# 03_-_Controller.net
KiCad netlist of a schematic drawn in Altium Designer
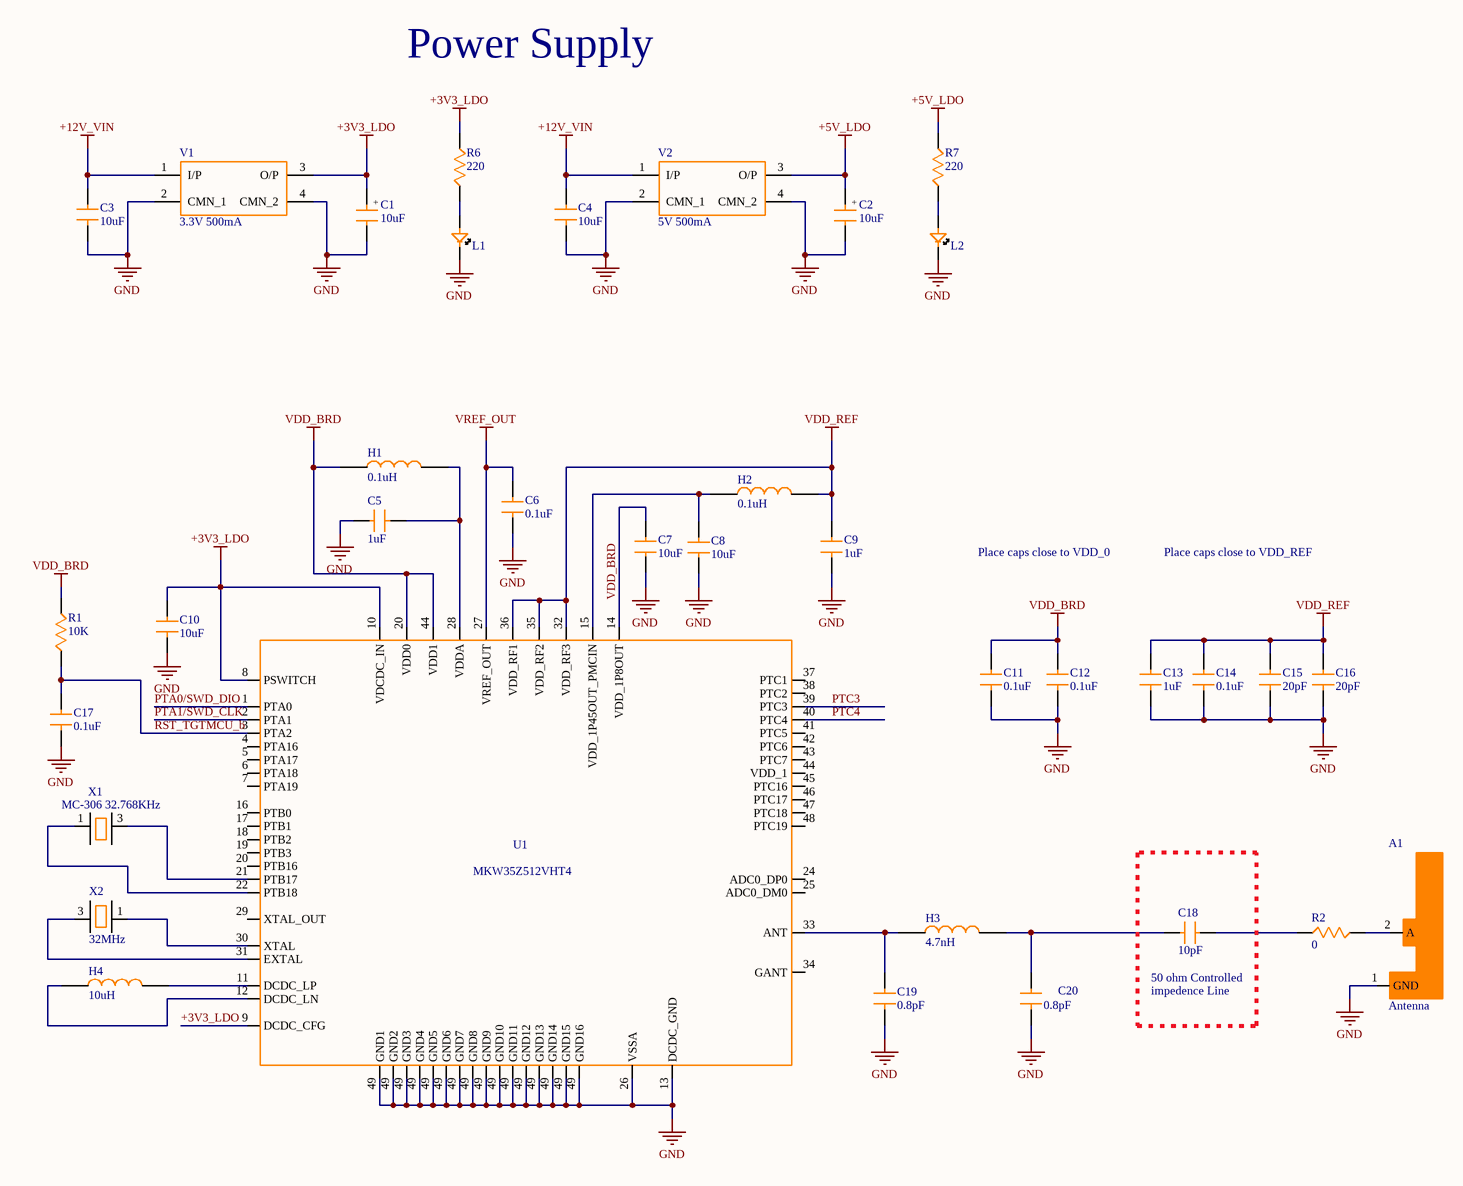
[diagram p0: [03] - Controller.SchDoc]

(export (version "E")
  (design (tool "Eeschema 10.0.6"))
  (components
    (comp (ref "A1")
      (value "Antenna")
      (footprint "Antenna")
      (libsource (lib "Joule_Library") (part "Antenna"))
    )
    (comp (ref "C1")
      (value "10uF")
      (footprint "C1206")
      (description "Tantalum Capacitors - Polymer SMD 10V 4.7uF 20% 1206 ESR=300mOhm")
      (fields
        (field (name "MANUFACTURER") "AVX")
        (field (name "MANUFACTURER PART NUMBER") "TCJK475M010R0300")
      )
      (libsource (lib "Joule_Library") (part "EIA_A-4.7uF,10V"))
    )
    (comp (ref "C2")
      (value "10uF")
      (footprint "C1206")
      (description "Tantalum Capacitors - Polymer SMD 10V 4.7uF 20% 1206 ESR=300mOhm")
      (fields
        (field (name "MANUFACTURER") "AVX")
        (field (name "MANUFACTURER PART NUMBER") "TCJK475M010R0300")
      )
      (libsource (lib "Joule_Library") (part "EIA_A-4.7uF,10V"))
    )
    (comp (ref "C3")
      (value "10uF")
      (footprint "C1206")
      (description "Multilayer Ceramic Capacitors MLCC - SMD/SMT 10uF Y5V -20/+80% 50V")
      (fields
        (field (name "MANUFACTURER") "Yageo")
        (field (name "MANUFACTURER PART NUMBER") "CC1210ZKY5V9BB106")
      )
      (libsource (lib "Joule_Library") (part "C_1206-10uF"))
    )
    (comp (ref "C4")
      (value "10uF")
      (footprint "C1206")
      (description "Multilayer Ceramic Capacitors MLCC - SMD/SMT 10uF Y5V -20/+80% 50V")
      (fields
        (field (name "MANUFACTURER") "Yageo")
        (field (name "MANUFACTURER PART NUMBER") "CC1210ZKY5V9BB106")
      )
      (libsource (lib "Joule_Library") (part "C_1206-10uF"))
    )
    (comp (ref "C5")
      (value "1uF")
      (footprint "C0805")
      (description "Multilayer Ceramic Capacitors MLCC - SMD/SMT 10V 1uF X7R 0805 10%")
      (fields
        (field (name "MANUFACTURER") "KEMET")
        (field (name "MANUFACTURER PART NUMBER") "C0805C105K8RAC7210")
      )
      (libsource (lib "Joule_Library") (part "C_0805-1uF"))
    )
    (comp (ref "C6")
      (value "0.1uF")
      (footprint "C0805")
      (description "Multilayer Ceramic Capacitors MLCC - SMD/SMT 0.1uF 10% 50V AEC-Q200")
      (fields
        (field (name "MANUFACTURER") "Yageo")
        (field (name "MANUFACTURER PART NUMBER") "AS0805KKX7R9BB104")
      )
      (libsource (lib "Joule_Library") (part "C_0805-0.1uF"))
    )
    (comp (ref "C7")
      (value "10uF")
      (footprint "C0805")
      (description "Multilayer Ceramic Capacitors MLCC - SMD/SMT 10uF 10% 25V")
      (fields
        (field (name "MANUFACTURER") "Yageo")
        (field (name "MANUFACTURER PART NUMBER") "CC0805KFX5R8BB106")
      )
      (libsource (lib "Joule_Library") (part "C_0805-10uF"))
    )
    (comp (ref "C8")
      (value "10uF")
      (footprint "C0805")
      (description "Multilayer Ceramic Capacitors MLCC - SMD/SMT 10uF 10% 25V")
      (fields
        (field (name "MANUFACTURER") "Yageo")
        (field (name "MANUFACTURER PART NUMBER") "CC0805KFX5R8BB106")
      )
      (libsource (lib "Joule_Library") (part "C_0805-10uF"))
    )
    (comp (ref "C9")
      (value "1uF")
      (footprint "C0805")
      (description "Multilayer Ceramic Capacitors MLCC - SMD/SMT 10V 1uF X7R 0805 10%")
      (fields
        (field (name "MANUFACTURER") "KEMET")
        (field (name "MANUFACTURER PART NUMBER") "C0805C105K8RAC7210")
      )
      (libsource (lib "Joule_Library") (part "C_0805-1uF"))
    )
    (comp (ref "C10")
      (value "10uF")
      (footprint "C1206")
      (description "Multilayer Ceramic Capacitors MLCC - SMD/SMT 10uF Y5V -20/+80% 50V")
      (fields
        (field (name "MANUFACTURER") "Yageo")
        (field (name "MANUFACTURER PART NUMBER") "CC1210ZKY5V9BB106")
      )
      (libsource (lib "Joule_Library") (part "C_1206-10uF"))
    )
    (comp (ref "C11")
      (value "0.1uF")
      (footprint "C0805")
      (description "Multilayer Ceramic Capacitors MLCC - SMD/SMT 0.1uF 10% 50V AEC-Q200")
      (fields
        (field (name "MANUFACTURER") "Yageo")
        (field (name "MANUFACTURER PART NUMBER") "AS0805KKX7R9BB104")
      )
      (libsource (lib "Joule_Library") (part "C_0805-0.1uF"))
    )
    (comp (ref "C12")
      (value "0.1uF")
      (footprint "C0805")
      (description "Multilayer Ceramic Capacitors MLCC - SMD/SMT 0.1uF 10% 50V AEC-Q200")
      (fields
        (field (name "MANUFACTURER") "Yageo")
        (field (name "MANUFACTURER PART NUMBER") "AS0805KKX7R9BB104")
      )
      (libsource (lib "Joule_Library") (part "C_0805-0.1uF"))
    )
    (comp (ref "C13")
      (value "1uF")
      (footprint "C0805")
      (description "Multilayer Ceramic Capacitors MLCC - SMD/SMT 10V 1uF X7R 0805 10%")
      (fields
        (field (name "MANUFACTURER") "KEMET")
        (field (name "MANUFACTURER PART NUMBER") "C0805C105K8RAC7210")
      )
      (libsource (lib "Joule_Library") (part "C_0805-1uF"))
    )
    (comp (ref "C14")
      (value "0.1uF")
      (footprint "C0805")
      (description "Multilayer Ceramic Capacitors MLCC - SMD/SMT 0.1uF 10% 50V AEC-Q200")
      (fields
        (field (name "MANUFACTURER") "Yageo")
        (field (name "MANUFACTURER PART NUMBER") "AS0805KKX7R9BB104")
      )
      (libsource (lib "Joule_Library") (part "C_0805-0.1uF"))
    )
    (comp (ref "C15")
      (value "20pF")
      (footprint "C0805")
      (description "Multilayer Ceramic Capacitors MLCC - SMD/SMT 20pF 100volts C0G 5%")
      (fields
        (field (name "MANUFACTURER") "Vishay / Vitramon")
        (field (name "MANUFACTURER PART NUMBER") "VJ0805A200JXBAC")
      )
      (libsource (lib "Joule_Library") (part "C_0805-20pF"))
    )
    (comp (ref "C16")
      (value "20pF")
      (footprint "C0805")
      (description "Multilayer Ceramic Capacitors MLCC - SMD/SMT 20pF 100volts C0G 5%")
      (fields
        (field (name "MANUFACTURER") "Vishay / Vitramon")
        (field (name "MANUFACTURER PART NUMBER") "VJ0805A200JXBAC")
      )
      (libsource (lib "Joule_Library") (part "C_0805-20pF"))
    )
    (comp (ref "C17")
      (value "0.1uF")
      (footprint "C0805")
      (description "Multilayer Ceramic Capacitors MLCC - SMD/SMT 0.1uF 10% 50V AEC-Q200")
      (fields
        (field (name "MANUFACTURER") "Yageo")
        (field (name "MANUFACTURER PART NUMBER") "AS0805KKX7R9BB104")
      )
      (libsource (lib "Joule_Library") (part "C_0805-0.1uF"))
    )
    (comp (ref "C18")
      (value "10pF")
      (footprint "C0805")
      (description "Multilayer Ceramic Capacitors MLCC - SMD/SMT 10uF 10% 25V")
      (fields
        (field (name "MANUFACTURER") "Yageo")
        (field (name "MANUFACTURER PART NUMBER") "CC0805KFX5R8BB106")
      )
      (libsource (lib "Joule_Library") (part "C_0805-10uF"))
    )
    (comp (ref "C19")
      (value "0.8pF")
      (footprint "C0805")
      (description "Multilayer Ceramic Capacitors MLCC - SMD/SMT 20pF 100volts C0G 5%")
      (fields
        (field (name "MANUFACTURER") "Vishay / Vitramon")
        (field (name "MANUFACTURER PART NUMBER") "VJ0805A200JXBAC")
      )
      (libsource (lib "Joule_Library") (part "C_0805-20pF"))
    )
    (comp (ref "C20")
      (value "0.8pF")
      (footprint "C0805")
      (description "Multilayer Ceramic Capacitors MLCC - SMD/SMT 20pF 100volts C0G 5%")
      (fields
        (field (name "MANUFACTURER") "Vishay / Vitramon")
        (field (name "MANUFACTURER PART NUMBER") "VJ0805A200JXBAC")
      )
      (libsource (lib "Joule_Library") (part "C_0805-20pF"))
    )
    (comp (ref "H1")
      (value "0.1uH")
      (footprint "I-0805")
      (description "Fixed Inductors .1uH 5%")
      (fields
        (field (name "MANUFACTURER") "Vishay / Dale")
        (field (name "MANUFACTURER PART NUMBER") "IMC0805ERR10J01")
      )
      (libsource (lib "Joule_Library") (part "I_0805-0.1uH"))
    )
    (comp (ref "H2")
      (value "0.1uH")
      (footprint "I-0805")
      (description "Fixed Inductors .1uH 5%")
      (fields
        (field (name "MANUFACTURER") "Vishay / Dale")
        (field (name "MANUFACTURER PART NUMBER") "IMC0805ERR10J01")
      )
      (libsource (lib "Joule_Library") (part "I_0805-0.1uH"))
    )
    (comp (ref "H3")
      (value "4.7nH")
      (footprint "I-0805")
      (description "Fixed Inductors 4.7nH")
      (fields (field (name "MANUFACTURER") "AVX") (field (name "MANUFACTURER PART NUMBER") "L08054R7DEWTR"))
      (libsource (lib "Joule_Library") (part "I_0805-4.7nH"))
    )
    (comp (ref "H4")
      (value "10uH")
      (footprint "SRN4018")
      (description "Fixed Inductors 10uH 20% SMD 4018")
      (fields (field (name "MANUFACTURER") "Bourns") (field (name "MANUFACTURER PART NUMBER") "SRN4018-100M"))
      (libsource (lib "Joule_Library") (part "SRN4018-100M"))
    )
    (comp (ref "L1")
      (value "599-0130-007F")
      (footprint "LED0805")
      (description "Standard LEDs - SMD SMD 0805 ORANGE")
      (fields (field (name "MANUFACTURER") "Dialight"))
      (libsource (lib "Joule_Library") (part "599-0130-007F"))
    )
    (comp (ref "L2")
      (value "599-0130-007F")
      (footprint "LED0805")
      (description "Standard LEDs - SMD SMD 0805 ORANGE")
      (fields (field (name "MANUFACTURER") "Dialight"))
      (libsource (lib "Joule_Library") (part "599-0130-007F"))
    )
    (comp (ref "R1")
      (value "10K")
      (footprint "R0805")
      (description "Thick Film Resistors - SMD 10K   OHM   1% 1/4W")
      (fields
        (field (name "MANUFACTURER") "Yageo")
        (field (name "MANUFACTURER PART NUMBER") "RC0805FR-7W10KL")
      )
      (libsource (lib "Joule_Library") (part "R_0805-10K"))
    )
    (comp (ref "R2")
      (value "0")
      (footprint "R0805")
      (description "Current Sense Resistors - SMD 0 ohm Jumper 1/2W")
      (fields
        (field (name "MANUFACTURER") "Yageo")
        (field (name "MANUFACTURER PART NUMBER") "PA0805-R-470RL")
      )
      (libsource (lib "Joule_Library") (part "R_0805-0"))
    )
    (comp (ref "R6")
      (value "220")
      (footprint "R0805")
      (description "Thin Film Resistors - SMD")
      (fields
        (field (name "MANUFACTURER") "Yageo")
        (field (name "MANUFACTURER PART NUMBER") "RT0805DRE07220RL")
      )
      (libsource (lib "Joule_Library") (part "R_0805-220"))
    )
    (comp (ref "R7")
      (value "220")
      (footprint "R0805")
      (description "Thin Film Resistors - SMD")
      (fields
        (field (name "MANUFACTURER") "Yageo")
        (field (name "MANUFACTURER PART NUMBER") "RT0805DRE07220RL")
      )
      (libsource (lib "Joule_Library") (part "R_0805-220"))
    )
    (comp (ref "U1")
      (value "MKW35Z512VHT4")
      (footprint "MKW35Z512VHT4")
      (fields (field (name "MANUFACTURER") "NXP Semiconductors"))
      (libsource (lib "Joule_Library") (part "MKW35Z512VHT4"))
    )
    (comp (ref "V1")
      (value "3.3V 500mA")
      (footprint "UA78M05/33-CDCYR")
      (description "Linear Voltage Regulators 3.3V 500mA Fixd Pos")
      (fields
        (field (name "MANUFACTURER") "Texas Instruments")
        (field (name "MANUFACTURER PART NUMBER") "UA78M33CDCYR")
      )
      (libsource (lib "Joule_Library") (part "UA78M33CDCYR"))
    )
    (comp (ref "V2")
      (value "5V 500mA")
      (footprint "UA78M05/33-CDCYR")
      (description "Linear Voltage Regulators 5.0V 500mA Fxd Pos")
      (fields
        (field (name "MANUFACTURER") "Texas Instruments")
        (field (name "MANUFACTURER PART NUMBER") "UA78M05CDCYR")
      )
      (libsource (lib "Joule_Library") (part "UA78M05CDCYR"))
    )
    (comp (ref "X1")
      (value "MC-306 32.768KHz")
      (footprint "MC-306_32.768KHz")
      (description "Crystals 32.768KHz 12.5pF 20ppm -40C +85C")
      (fields
        (field (name "MANUFACTURER") "Epson Timing")
        (field (name "MANUFACTURER PART NUMBER") "MC-306 32.7680K-A0:ROHS")
      )
      (libsource (lib "Joule_Library") (part "MC-306 32.768KHz"))
    )
    (comp (ref "X2")
      (value "32MHz")
      (footprint "ECS-250-18-30B-JTN-TR")
      (description "Crystals 25MHz 20ppm 18pF -40C +85C")
      (fields
        (field (name "MANUFACTURER") "ECS")
        (field (name "MANUFACTURER PART NUMBER") "ECS-250-18-30B-JTN-TR")
      )
      (libsource (lib "Joule_Library") (part "ECS-25MHz"))
    )
  )
  (nets
    (net (code "1") (name "+3V3_LDO") (class "Default")
      (node (ref "C1") (pin "1") (pinfunction "1_1") (pintype "passive"))
      (node (ref "C10") (pin "2") (pinfunction "2_2") (pintype "passive"))
      (node (ref "R6") (pin "2") (pinfunction "2_2") (pintype "passive"))
      (node (ref "U1") (pin "10") (pinfunction "VDCDC_IN_10") (pintype "passive"))
      (node (ref "U1") (pin "8") (pinfunction "PSWITCH_8") (pintype "passive"))
      (node (ref "U1") (pin "9") (pinfunction "DCDC_CFG_9") (pintype "passive"))
      (node (ref "V1") (pin "3") (pinfunction "O/P_3") (pintype "passive"))
    )
    (net (code "2") (name "+5V_LDO") (class "Default")
      (node (ref "C2") (pin "1") (pinfunction "1_1") (pintype "passive"))
      (node (ref "R7") (pin "2") (pinfunction "2_2") (pintype "passive"))
      (node (ref "V2") (pin "3") (pinfunction "O/P_3") (pintype "passive"))
    )
    (net (code "3") (name "+12V_VIN") (class "Default")
      (node (ref "C3") (pin "2") (pinfunction "2_2") (pintype "passive"))
      (node (ref "C4") (pin "2") (pinfunction "2_2") (pintype "passive"))
      (node (ref "V1") (pin "1") (pinfunction "I/P_1") (pintype "passive"))
      (node (ref "V2") (pin "1") (pinfunction "I/P_1") (pintype "passive"))
    )
    (net (code "4") (name "/PTA0{slash}SWD_DIO") (class "Default")
      (node (ref "U1") (pin "1") (pinfunction "PTA0_1") (pintype "passive"))
    )
    (net (code "5") (name "/PTA1{slash}SWD_CLK") (class "Default")
      (node (ref "U1") (pin "2") (pinfunction "PTA1_2") (pintype "passive"))
    )
    (net (code "6") (name "/PTC3") (class "Default")
      (node (ref "U1") (pin "39") (pinfunction "PTC3_39") (pintype "passive"))
    )
    (net (code "7") (name "/PTC4") (class "Default")
      (node (ref "U1") (pin "40") (pinfunction "PTC4_40") (pintype "passive"))
    )
    (net (code "8") (name "/RST_TGTMCU_b") (class "Default")
      (node (ref "C17") (pin "2") (pinfunction "2_2") (pintype "passive"))
      (node (ref "R1") (pin "1") (pinfunction "1_1") (pintype "passive"))
      (node (ref "U1") (pin "3") (pinfunction "PTA2_3") (pintype "passive"))
    )
    (net (code "9") (name "GND") (class "Default")
      (node (ref "A1") (pin "1") (pinfunction "GND_1") (pintype "passive"))
      (node (ref "C1") (pin "2") (pinfunction "2_2") (pintype "passive"))
      (node (ref "C10") (pin "1") (pinfunction "1_1") (pintype "passive"))
      (node (ref "C11") (pin "1") (pinfunction "1_1") (pintype "passive"))
      (node (ref "C12") (pin "1") (pinfunction "1_1") (pintype "passive"))
      (node (ref "C13") (pin "1") (pinfunction "1_1") (pintype "passive"))
      (node (ref "C14") (pin "1") (pinfunction "1_1") (pintype "passive"))
      (node (ref "C15") (pin "1") (pinfunction "1_1") (pintype "passive"))
      (node (ref "C16") (pin "1") (pinfunction "1_1") (pintype "passive"))
      (node (ref "C17") (pin "1") (pinfunction "1_1") (pintype "passive"))
      (node (ref "C19") (pin "1") (pinfunction "1_1") (pintype "passive"))
      (node (ref "C2") (pin "2") (pinfunction "2_2") (pintype "passive"))
      (node (ref "C20") (pin "1") (pinfunction "1_1") (pintype "passive"))
      (node (ref "C3") (pin "1") (pinfunction "1_1") (pintype "passive"))
      (node (ref "C4") (pin "1") (pinfunction "1_1") (pintype "passive"))
      (node (ref "C5") (pin "2") (pinfunction "2_2") (pintype "passive"))
      (node (ref "C6") (pin "1") (pinfunction "1_1") (pintype "passive"))
      (node (ref "C7") (pin "1") (pinfunction "1_1") (pintype "passive"))
      (node (ref "C8") (pin "1") (pinfunction "1_1") (pintype "passive"))
      (node (ref "C9") (pin "1") (pinfunction "1_1") (pintype "passive"))
      (node (ref "L1") (pin "2") (pinfunction "2_2") (pintype "passive"))
      (node (ref "L2") (pin "2") (pinfunction "2_2") (pintype "passive"))
      (node (ref "U1") (pin "13") (pinfunction "DCDC_GND_13") (pintype "passive"))
      (node (ref "U1") (pin "26") (pinfunction "VSSA_26") (pintype "passive"))
      (node (ref "U1") (pin "49") (pinfunction "GND4_49") (pintype "passive"))
      (node (ref "V1") (pin "2") (pinfunction "CMN_1_2") (pintype "passive"))
      (node (ref "V1") (pin "4") (pinfunction "CMN_2_4") (pintype "passive"))
      (node (ref "V2") (pin "2") (pinfunction "CMN_1_2") (pintype "passive"))
      (node (ref "V2") (pin "4") (pinfunction "CMN_2_4") (pintype "passive"))
    )
    (net (code "10") (name "Net-(A1-A)") (class "Default")
      (node (ref "A1") (pin "2") (pinfunction "A_2") (pintype "passive"))
      (node (ref "R2") (pin "2") (pinfunction "2_2") (pintype "passive"))
    )
    (net (code "11") (name "Net-(C18-Pad1)") (class "Default")
      (node (ref "C18") (pin "1") (pinfunction "1_1") (pintype "passive"))
      (node (ref "R2") (pin "1") (pinfunction "1_1") (pintype "passive"))
    )
    (net (code "12") (name "Net-(C18-Pad2)") (class "Default")
      (node (ref "C18") (pin "2") (pinfunction "2_2") (pintype "passive"))
      (node (ref "C20") (pin "2") (pinfunction "2_2") (pintype "passive"))
      (node (ref "H3") (pin "2") (pinfunction "2_2") (pintype "passive"))
    )
    (net (code "13") (name "Net-(L1-Pad1)") (class "Default")
      (node (ref "L1") (pin "1") (pinfunction "1_1") (pintype "passive"))
      (node (ref "R6") (pin "1") (pinfunction "1_1") (pintype "passive"))
    )
    (net (code "14") (name "Net-(L2-Pad1)") (class "Default")
      (node (ref "L2") (pin "1") (pinfunction "1_1") (pintype "passive"))
      (node (ref "R7") (pin "1") (pinfunction "1_1") (pintype "passive"))
    )
    (net (code "15") (name "Net-(U1-ANT)") (class "Default")
      (node (ref "C19") (pin "2") (pinfunction "2_2") (pintype "passive"))
      (node (ref "H3") (pin "1") (pinfunction "1_1") (pintype "passive"))
      (node (ref "U1") (pin "33") (pinfunction "ANT_33") (pintype "passive"))
    )
    (net (code "16") (name "Net-(U1-DCDC_LN)") (class "Default")
      (node (ref "H4") (pin "1") (pinfunction "1_1") (pintype "passive"))
      (node (ref "U1") (pin "12") (pinfunction "DCDC_LN_12") (pintype "passive"))
    )
    (net (code "17") (name "Net-(U1-DCDC_LP)") (class "Default")
      (node (ref "H4") (pin "2") (pinfunction "2_2") (pintype "passive"))
      (node (ref "U1") (pin "11") (pinfunction "DCDC_LP_11") (pintype "passive"))
    )
    (net (code "18") (name "Net-(U1-EXTAL)") (class "Default")
      (node (ref "U1") (pin "31") (pinfunction "EXTAL_31") (pintype "passive"))
      (node (ref "X2") (pin "3") (pinfunction "3_3") (pintype "passive"))
    )
    (net (code "19") (name "Net-(U1-PTB17)") (class "Default")
      (node (ref "U1") (pin "21") (pinfunction "PTB17_21") (pintype "passive"))
      (node (ref "X1") (pin "3") (pinfunction "3_3") (pintype "passive"))
    )
    (net (code "20") (name "Net-(U1-PTB18)") (class "Default")
      (node (ref "U1") (pin "22") (pinfunction "PTB18_22") (pintype "passive"))
      (node (ref "X1") (pin "1") (pinfunction "1_1") (pintype "passive"))
    )
    (net (code "21") (name "Net-(U1-VDDA)") (class "Default")
      (node (ref "C5") (pin "1") (pinfunction "1_1") (pintype "passive"))
      (node (ref "H1") (pin "2") (pinfunction "2_2") (pintype "passive"))
      (node (ref "U1") (pin "28") (pinfunction "VDDA_28") (pintype "passive"))
    )
    (net (code "22") (name "Net-(U1-VDD_1P45OUT_PMCIN)") (class "Default")
      (node (ref "C8") (pin "2") (pinfunction "2_2") (pintype "passive"))
      (node (ref "H2") (pin "1") (pinfunction "1_1") (pintype "passive"))
      (node (ref "U1") (pin "15") (pinfunction "VDD_1P45OUT_PMCIN_15") (pintype "passive"))
    )
    (net (code "23") (name "Net-(U1-XTAL)") (class "Default")
      (node (ref "U1") (pin "30") (pinfunction "XTAL_30") (pintype "passive"))
      (node (ref "X2") (pin "1") (pinfunction "1_1") (pintype "passive"))
    )
    (net (code "24") (name "VDD_BRD") (class "Default")
      (node (ref "C11") (pin "2") (pinfunction "2_2") (pintype "passive"))
      (node (ref "C12") (pin "2") (pinfunction "2_2") (pintype "passive"))
      (node (ref "C7") (pin "2") (pinfunction "2_2") (pintype "passive"))
      (node (ref "H1") (pin "1") (pinfunction "1_1") (pintype "passive"))
      (node (ref "R1") (pin "2") (pinfunction "2_2") (pintype "passive"))
      (node (ref "U1") (pin "14") (pinfunction "VDD_1P8OUT_14") (pintype "passive"))
      (node (ref "U1") (pin "20") (pinfunction "VDD0_20") (pintype "passive"))
      (node (ref "U1") (pin "44") (pinfunction "VDD1_44") (pintype "passive"))
    )
    (net (code "25") (name "VDD_REF") (class "Default")
      (node (ref "C13") (pin "2") (pinfunction "2_2") (pintype "passive"))
      (node (ref "C14") (pin "2") (pinfunction "2_2") (pintype "passive"))
      (node (ref "C15") (pin "2") (pinfunction "2_2") (pintype "passive"))
      (node (ref "C16") (pin "2") (pinfunction "2_2") (pintype "passive"))
      (node (ref "C9") (pin "2") (pinfunction "2_2") (pintype "passive"))
      (node (ref "H2") (pin "2") (pinfunction "2_2") (pintype "passive"))
      (node (ref "U1") (pin "32") (pinfunction "VDD_RF3_32") (pintype "passive"))
      (node (ref "U1") (pin "35") (pinfunction "VDD_RF2_35") (pintype "passive"))
      (node (ref "U1") (pin "36") (pinfunction "VDD_RF1_36") (pintype "passive"))
    )
    (net (code "26") (name "VREF_OUT") (class "Default")
      (node (ref "C6") (pin "2") (pinfunction "2_2") (pintype "passive"))
      (node (ref "U1") (pin "27") (pinfunction "VREF_OUT_27") (pintype "passive"))
    )
    (net (code "27") (name "unconnected-(U1-ADC0_DM0-Pad25)") (class "Default")
      (node (ref "U1") (pin "25") (pinfunction "ADC0_DM0_25") (pintype "passive"))
    )
    (net (code "28") (name "unconnected-(U1-ADC0_DP0-Pad24)") (class "Default")
      (node (ref "U1") (pin "24") (pinfunction "ADC0_DP0_24") (pintype "passive"))
    )
    (net (code "29") (name "unconnected-(U1-GANT-Pad34)") (class "Default")
      (node (ref "U1") (pin "34") (pinfunction "GANT_34") (pintype "passive"))
    )
    (net (code "30") (name "unconnected-(U1-PTA16-Pad4)") (class "Default")
      (node (ref "U1") (pin "4") (pinfunction "PTA16_4") (pintype "passive"))
    )
    (net (code "31") (name "unconnected-(U1-PTA17-Pad5)") (class "Default")
      (node (ref "U1") (pin "5") (pinfunction "PTA17_5") (pintype "passive"))
    )
    (net (code "32") (name "unconnected-(U1-PTA18-Pad6)") (class "Default")
      (node (ref "U1") (pin "6") (pinfunction "PTA18_6") (pintype "passive"))
    )
    (net (code "33") (name "unconnected-(U1-PTA19-Pad7)") (class "Default")
      (node (ref "U1") (pin "7") (pinfunction "PTA19_7") (pintype "passive"))
    )
    (net (code "34") (name "unconnected-(U1-PTB0-Pad16)") (class "Default")
      (node (ref "U1") (pin "16") (pinfunction "PTB0_16") (pintype "passive"))
    )
    (net (code "35") (name "unconnected-(U1-PTB1-Pad17)") (class "Default")
      (node (ref "U1") (pin "17") (pinfunction "PTB1_17") (pintype "passive"))
    )
    (net (code "36") (name "unconnected-(U1-PTB2-Pad18)") (class "Default")
      (node (ref "U1") (pin "18") (pinfunction "PTB2_18") (pintype "passive"))
    )
    (net (code "37") (name "unconnected-(U1-PTB3-Pad19)") (class "Default")
      (node (ref "U1") (pin "19") (pinfunction "PTB3_19") (pintype "passive"))
    )
    (net (code "38") (name "unconnected-(U1-PTB16-Pad20)") (class "Default")
      (node (ref "U1") (pin "20") (pinfunction "PTB16_20") (pintype "passive"))
    )
    (net (code "39") (name "unconnected-(U1-PTC1-Pad37)") (class "Default")
      (node (ref "U1") (pin "37") (pinfunction "PTC1_37") (pintype "passive"))
    )
    (net (code "40") (name "unconnected-(U1-PTC2-Pad38)") (class "Default")
      (node (ref "U1") (pin "38") (pinfunction "PTC2_38") (pintype "passive"))
    )
    (net (code "41") (name "unconnected-(U1-PTC5-Pad41)") (class "Default")
      (node (ref "U1") (pin "41") (pinfunction "PTC5_41") (pintype "passive"))
    )
    (net (code "42") (name "unconnected-(U1-PTC6-Pad42)") (class "Default")
      (node (ref "U1") (pin "42") (pinfunction "PTC6_42") (pintype "passive"))
    )
    (net (code "43") (name "unconnected-(U1-PTC7-Pad43)") (class "Default")
      (node (ref "U1") (pin "43") (pinfunction "PTC7_43") (pintype "passive"))
    )
    (net (code "44") (name "unconnected-(U1-PTC16-Pad45)") (class "Default")
      (node (ref "U1") (pin "45") (pinfunction "PTC16_45") (pintype "passive"))
    )
    (net (code "45") (name "unconnected-(U1-PTC17-Pad46)") (class "Default")
      (node (ref "U1") (pin "46") (pinfunction "PTC17_46") (pintype "passive"))
    )
    (net (code "46") (name "unconnected-(U1-PTC18-Pad47)") (class "Default")
      (node (ref "U1") (pin "47") (pinfunction "PTC18_47") (pintype "passive"))
    )
    (net (code "47") (name "unconnected-(U1-PTC19-Pad48)") (class "Default")
      (node (ref "U1") (pin "48") (pinfunction "PTC19_48") (pintype "passive"))
    )
    (net (code "48") (name "unconnected-(U1-VDD_1-Pad44)") (class "Default")
      (node (ref "U1") (pin "44") (pinfunction "VDD_1_44") (pintype "passive"))
    )
    (net (code "49") (name "unconnected-(U1-XTAL_OUT-Pad29)") (class "Default")
      (node (ref "U1") (pin "29") (pinfunction "XTAL_OUT_29") (pintype "passive"))
    )
  )
)
